# Regulators.net
KiCad netlist of a schematic drawn in Altium Designer
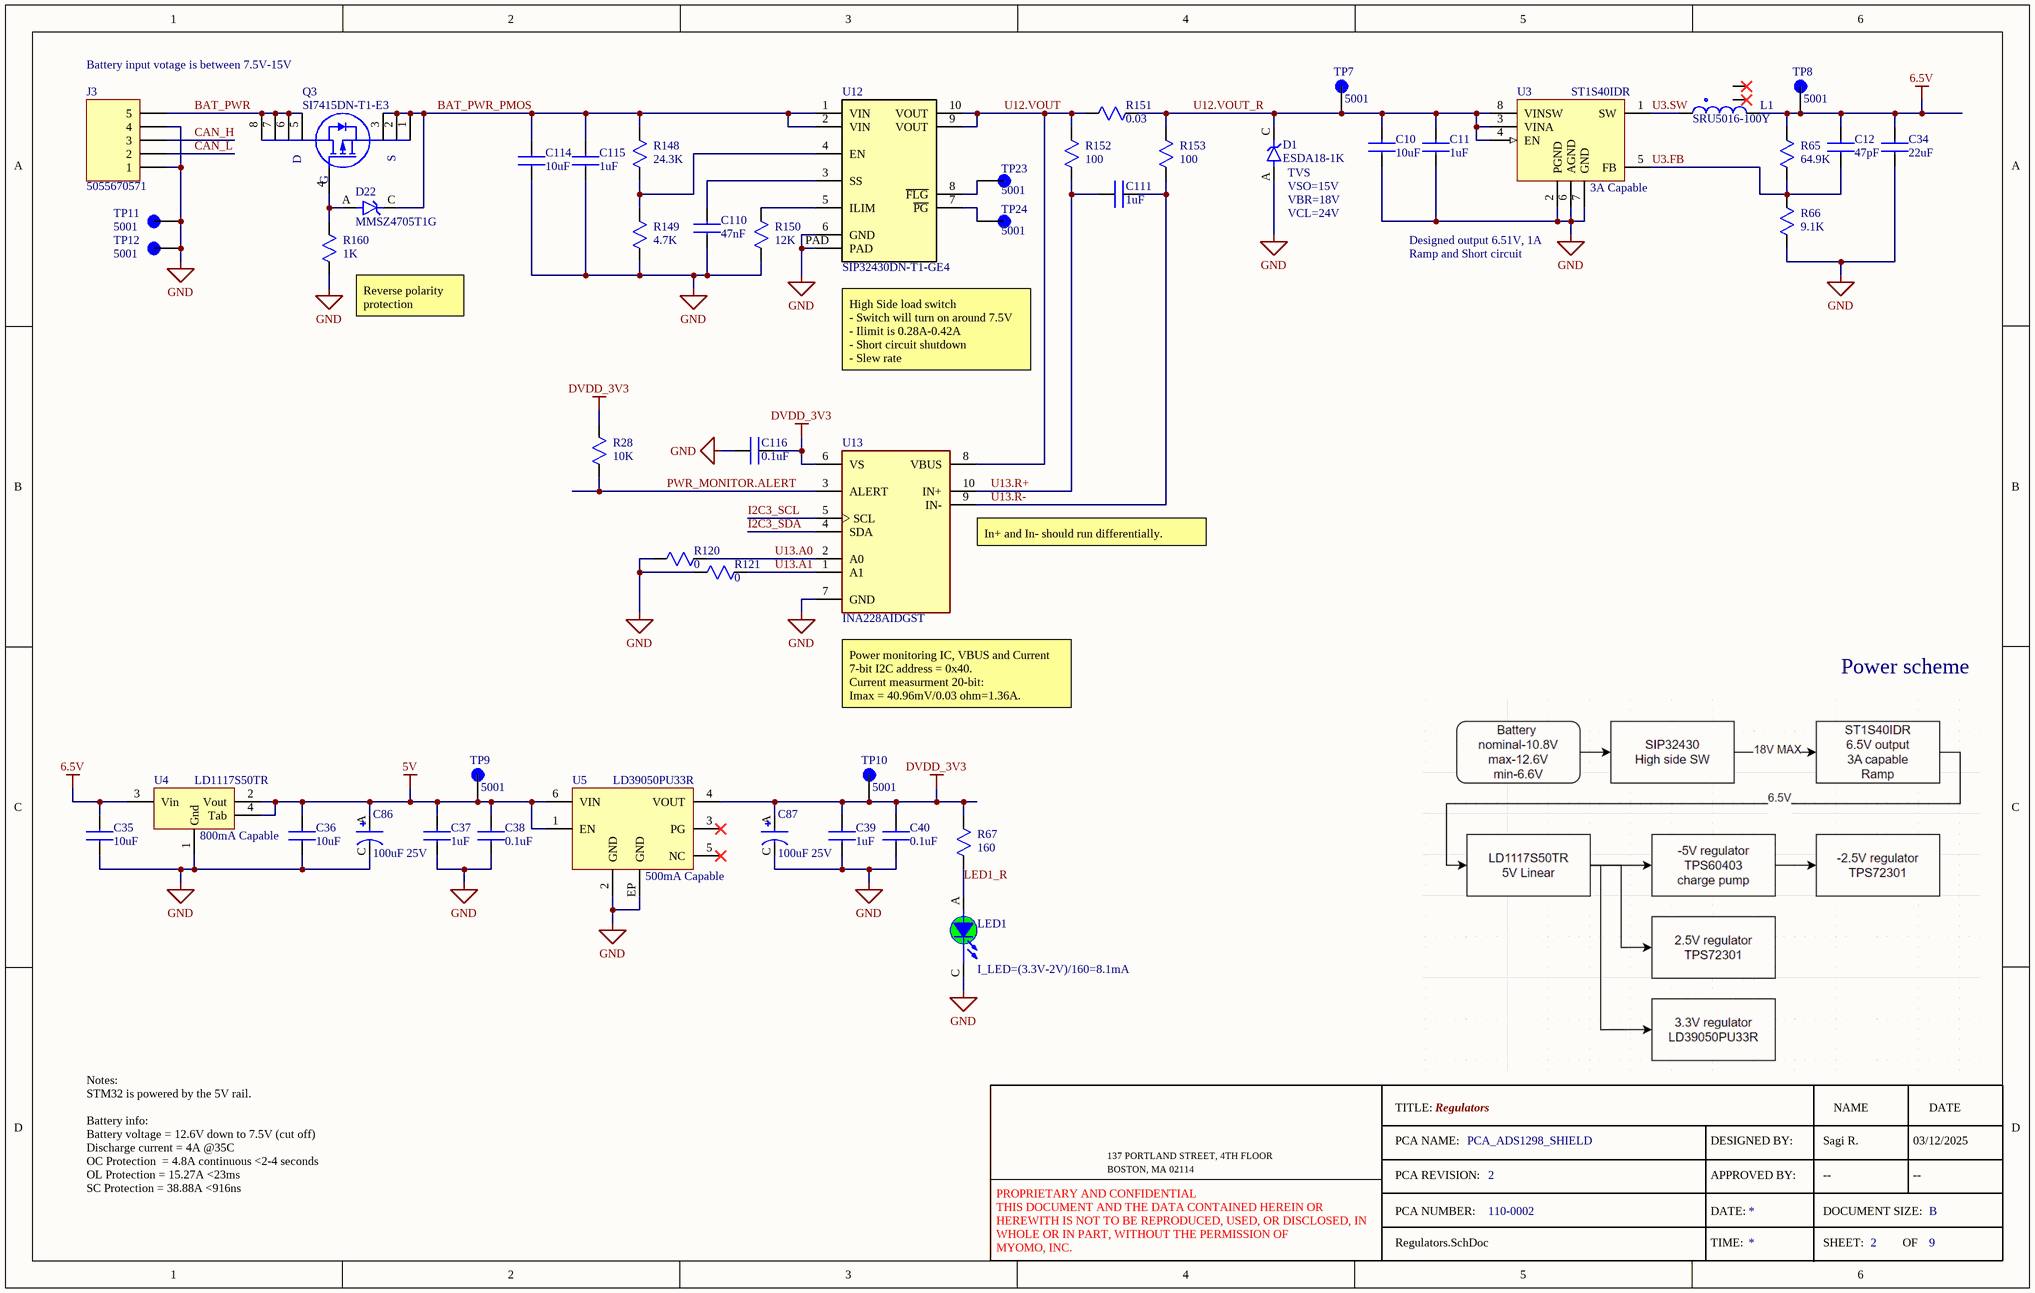
[diagram p0: Regulators.SchDoc]

(export (version "E")
  (design (tool "Eeschema 10.0.6"))
  (components
    (comp (ref "C10")
      (value "10uF")
      (footprint "1210")
      (description "CAP CER 10UF 25V X7R 1210")
      (fields (field (name "MFG") "SUMSUNG"))
      (libsource (lib "Myomo_SCH_Library") (part "C_1210_CER_10uF_25V_X7R"))
    )
    (comp (ref "C11")
      (value "1uF")
      (footprint "0603")
      (description "CAP CER 1UF 50V X7R 0603")
      (fields (field (name "MFG") "YAGEO"))
      (libsource (lib "Myomo_SCH_Library") (part "C_0603_CER_1uF_50V_X7R"))
    )
    (comp (ref "C12")
      (value "47pF")
      (footprint "0603")
      (description "CAP CER 47PF 100V C0G/NP0 0603")
      (fields (field (name "MFG") "KEMET"))
      (libsource (lib "Myomo_SCH_Library") (part "C_0603_CER_47pF_100V_COG"))
    )
    (comp (ref "C34")
      (value "22uF")
      (footprint "1210")
      (description "CAP CER 22UF 25V X7R 1210")
      (fields (field (name "MFG") "SUMSUNG"))
      (libsource (lib "Myomo_SCH_Library") (part "C_1210_CER_22uF_25V_X7R"))
    )
    (comp (ref "C35")
      (value "10uF")
      (footprint "1210")
      (description "CAP CER 10UF 25V X7R 1210")
      (fields (field (name "MFG") "SUMSUNG"))
      (libsource (lib "Myomo_SCH_Library") (part "C_1210_CER_10uF_25V_X7R"))
    )
    (comp (ref "C36")
      (value "10uF")
      (footprint "1210")
      (description "CAP CER 10UF 25V X7R 1210")
      (fields (field (name "MFG") "SUMSUNG"))
      (libsource (lib "Myomo_SCH_Library") (part "C_1210_CER_10uF_25V_X7R"))
    )
    (comp (ref "C37")
      (value "1uF")
      (footprint "0603")
      (description "CAP CER 1UF 50V X7R 0603")
      (fields (field (name "MFG") "YAGEO"))
      (libsource (lib "Myomo_SCH_Library") (part "C_0603_CER_1uF_50V_X7R"))
    )
    (comp (ref "C38")
      (value "0.1uF")
      (footprint "0402")
      (description "CAP CER 0.1UF 50V X7R 0402")
      (fields (field (name "MFG") "Samsung"))
      (libsource (lib "Myomo_SCH_Library") (part "C_0402_CER_0.1uF_50V_X7R"))
    )
    (comp (ref "C39")
      (value "1uF")
      (footprint "0603")
      (description "CAP CER 1UF 50V X7R 0603")
      (fields (field (name "MFG") "YAGEO"))
      (libsource (lib "Myomo_SCH_Library") (part "C_0603_CER_1uF_50V_X7R"))
    )
    (comp (ref "C40")
      (value "0.1uF")
      (footprint "0402")
      (description "CAP CER 0.1UF 50V X7R 0402")
      (fields (field (name "MFG") "Samsung"))
      (libsource (lib "Myomo_SCH_Library") (part "C_0402_CER_0.1uF_50V_X7R"))
    )
    (comp (ref "C86")
      (value "100uF 25V")
      (footprint "C_2917_TANT_100uF_25V")
      (description "CAP TANT POLY 100UF 25V 2917")
      (fields (field (name "MFG") "AVX Corporation"))
      (libsource (lib "Myomo_SCH_Library") (part "C_2917_TANT_100uF_25V"))
    )
    (comp (ref "C87")
      (value "100uF 25V")
      (footprint "C_2917_TANT_100uF_25V")
      (description "CAP TANT POLY 100UF 25V 2917")
      (fields (field (name "MFG") "AVX Corporation"))
      (libsource (lib "Myomo_SCH_Library") (part "C_2917_TANT_100uF_25V"))
    )
    (comp (ref "C110")
      (value "47nF")
      (footprint "0402")
      (description "CAP CER 47nF 50V X7R 0402")
      (fields (field (name "MFG") "TDK"))
      (libsource (lib "Myomo_SCH_Library") (part "C_0402_CER_47nF_50V_X7R"))
    )
    (comp (ref "C111")
      (value "1uF")
      (footprint "0603")
      (description "CAP CER 1UF 50V X7R 0603")
      (fields (field (name "MFG") "YAGEO"))
      (libsource (lib "") (part "C_0603_CER_1uF_50V_X7R_1"))
    )
    (comp (ref "C114")
      (value "10uF")
      (footprint "1210")
      (description "CAP CER 10UF 25V X7R 1210")
      (fields (field (name "MFG") "SUMSUNG"))
      (libsource (lib "Myomo_SCH_Library") (part "C_1210_CER_10uF_25V_X7R"))
    )
    (comp (ref "C115")
      (value "1uF")
      (footprint "0603")
      (description "CAP CER 1UF 50V X7R 0603")
      (fields (field (name "MFG") "YAGEO"))
      (libsource (lib "Myomo_SCH_Library") (part "C_0603_CER_1uF_50V_X7R"))
    )
    (comp (ref "C116")
      (value "0.1uF")
      (footprint "0402")
      (description "CAP CER 0.1UF 50V X7R 0402")
      (fields (field (name "MFG") "Samsung"))
      (libsource (lib "") (part "C_0402_CER_0.1uF_50V_X7R_1"))
    )
    (comp (ref "D1")
      (value "ESDA18-1K")
      (footprint "D_TVS_18V_400W")
      (description "TVS DIODE 15VWM 34VC SOD523")
      (fields (field (name "MFG") "STMicroelectronics"))
      (libsource (lib "Myomo_SCH_Library") (part "D_TVS_18V_400W"))
    )
    (comp (ref "D22")
      (value "MMSZ4705T1G")
      (footprint "D_ZENER_18V_500mW")
      (description "DIODE ZENER 18V 500MW SOD123")
      (fields (field (name "MFG") "Onsemi"))
      (libsource (lib "Myomo_SCH_Library") (part "D_ZENER_18V_500mW"))
    )
    (comp (ref "J3")
      (value "5055670571")
      (footprint "J_MOLEX_5055670571")
      (description "CONN HEADER SMD R/A 5POS 1.25MM")
      (fields (field (name "MFG") "Molex"))
      (libsource (lib "Myomo_SCH_Library") (part "J_MOLEX_5055670571"))
    )
    (comp (ref "L1")
      (value "SRU5016-100Y")
      (footprint "L_10UH_84m_1A")
      (description "FIXED IND 10UH 1A 84 MOHM SMD")
      (fields (field (name "MFG") "Bourns Inc."))
      (libsource (lib "Myomo_SCH_Library") (part "L_10UH_84m_1A"))
    )
    (comp (ref "LED1")
      (value "D_LED_GREEN_LTST")
      (footprint "D_LED_GREEN_LTST")
      (description "LED GREEN CLEAR 0603 SMD")
      (fields (field (name "MFG") "Lite-On Inc."))
      (libsource (lib "Myomo_SCH_Library") (part "D_LED_GREEN_LTST"))
    )
    (comp (ref "Q3")
      (value "SI7415DN-T1-E3")
      (footprint "Q_PMOSFET_SI7415DN-T1-E3")
      (description "MOSFET P-CH 60V 3.6A PPAK1212-8")
      (fields (field (name "MFG") "Vishay"))
      (libsource (lib "Myomo_SCH_Library") (part "Q_PMOSFET_SI7415DN-T1-E3"))
    )
    (comp (ref "R28")
      (value "10K")
      (footprint "0402")
      (description "RES SMD 10K OHM 1% 1/10W 0402")
      (fields (field (name "MFG") "Panasonic"))
      (libsource (lib "Myomo_SCH_Library") (part "R_0402_10K_1%_1/10W"))
    )
    (comp (ref "R65")
      (value "64.9K")
      (footprint "0603")
      (description "RES 64.9K OHM 1% 1/10W 0603")
      (fields (field (name "MFG") "YAGEO"))
      (libsource (lib "Myomo_SCH_Library") (part "R_0603_64.9K_1%_1/10W"))
    )
    (comp (ref "R66")
      (value "9.1K")
      (footprint "0603")
      (description "RES 9.1K OHM 1% 1/10W 0603")
      (fields (field (name "MFG") "YAGEO"))
      (libsource (lib "Myomo_SCH_Library") (part "R_0603_9.1K_1%_1/10W"))
    )
    (comp (ref "R67")
      (value "160")
      (footprint "0603")
      (description "RES 160 OHM 1% 1/10W 0603")
      (fields (field (name "MFG") "YAGEO"))
      (libsource (lib "Myomo_SCH_Library") (part "R_0603_160_1%_1/10W"))
    )
    (comp (ref "R120")
      (value "0")
      (footprint "0402")
      (description "RES 0 OHM JUMPER 1/10W 0402")
      (fields (field (name "MFG") "YAGEO"))
      (libsource (lib "Myomo_SCH_Library") (part "R_0402_0"))
    )
    (comp (ref "R121")
      (value "0")
      (footprint "0402")
      (description "RES 0 OHM JUMPER 1/10W 0402")
      (fields (field (name "MFG") "YAGEO"))
      (libsource (lib "Myomo_SCH_Library") (part "R_0402_0"))
    )
    (comp (ref "R148")
      (value "24.3K")
      (footprint "0402")
      (description "RES SMD 24.3K OHM 1% 1/10W 0402")
      (fields (field (name "MFG") "Panasonic"))
      (libsource (lib "Myomo_SCH_Library") (part "R_0402_24.3K_1%_1/10W"))
    )
    (comp (ref "R149")
      (value "4.7K")
      (footprint "0402")
      (description "RES SMD 4.7K OHM 1% 1/10W 0402")
      (fields (field (name "MFG") "Panasonic"))
      (libsource (lib "Myomo_SCH_Library") (part "R_0402_4.7K_1%_1/10W"))
    )
    (comp (ref "R150")
      (value "12K")
      (footprint "0402")
      (description "RES SMD 12K OHM 1% 1/10W 0402")
      (fields (field (name "MFG") "Panasonic"))
      (libsource (lib "Myomo_SCH_Library") (part "R_0402_12K_1%_1/10W"))
    )
    (comp (ref "R151")
      (value "0.03")
      (footprint "1206")
      (description "RES 0.03 OHM 0.5% 1W 1206")
      (fields (field (name "MFG") "Vishay"))
      (libsource (lib "Myomo_SCH_Library") (part "R_1206_0.03_0.5%_1W"))
    )
    (comp (ref "R152")
      (value "100")
      (footprint "0402")
      (description "RES SMD 100 OHM 1% 1/10W 0402")
      (fields (field (name "MFG") "Panasonic"))
      (libsource (lib "Myomo_SCH_Library") (part "R_0402_100_1%_1/10W"))
    )
    (comp (ref "R153")
      (value "100")
      (footprint "0402")
      (description "RES SMD 100 OHM 1% 1/10W 0402")
      (fields (field (name "MFG") "Panasonic"))
      (libsource (lib "Myomo_SCH_Library") (part "R_0402_100_1%_1/10W"))
    )
    (comp (ref "R160")
      (value "1K")
      (footprint "0603")
      (description "RES 1K OHM 1% 1/10W 0603")
      (fields (field (name "MFG") "YAGEO"))
      (libsource (lib "Myomo_SCH_Library") (part "R_0603_1K_1%_1/10W"))
    )
    (comp (ref "TP7")
      (value "5001")
      (footprint "TP_CLIP_BLK_5001")
      (description "PC TEST POINT MINIATURE BLACK")
      (fields (field (name "MFG") "Keystone Electronics"))
      (libsource (lib "Myomo_SCH_Library") (part "TP_CLIP_BLK_5001"))
    )
    (comp (ref "TP8")
      (value "5001")
      (footprint "TP_CLIP_BLK_5001")
      (description "PC TEST POINT MINIATURE BLACK")
      (fields (field (name "MFG") "Keystone Electronics"))
      (libsource (lib "Myomo_SCH_Library") (part "TP_CLIP_BLK_5001"))
    )
    (comp (ref "TP9")
      (value "5001")
      (footprint "TP_CLIP_BLK_5001")
      (description "PC TEST POINT MINIATURE BLACK")
      (fields (field (name "MFG") "Keystone Electronics"))
      (libsource (lib "Myomo_SCH_Library") (part "TP_CLIP_BLK_5001"))
    )
    (comp (ref "TP10")
      (value "5001")
      (footprint "TP_CLIP_BLK_5001")
      (description "PC TEST POINT MINIATURE BLACK")
      (fields (field (name "MFG") "Keystone Electronics"))
      (libsource (lib "Myomo_SCH_Library") (part "TP_CLIP_BLK_5001"))
    )
    (comp (ref "TP11")
      (value "5001")
      (footprint "TP_CLIP_BLK_5001")
      (description "PC TEST POINT MINIATURE BLACK")
      (fields (field (name "MFG") "Keystone Electronics"))
      (libsource (lib "Myomo_SCH_Library") (part "TP_CLIP_BLK_5001"))
    )
    (comp (ref "TP12")
      (value "5001")
      (footprint "TP_CLIP_BLK_5001")
      (description "PC TEST POINT MINIATURE BLACK")
      (fields (field (name "MFG") "Keystone Electronics"))
      (libsource (lib "Myomo_SCH_Library") (part "TP_CLIP_BLK_5001"))
    )
    (comp (ref "TP23")
      (value "5001")
      (footprint "TP_CLIP_BLK_5001")
      (description "PC TEST POINT MINIATURE BLACK")
      (fields (field (name "MFG") "Keystone Electronics"))
      (libsource (lib "Myomo_SCH_Library") (part "TP_CLIP_BLK_5001"))
    )
    (comp (ref "TP24")
      (value "5001")
      (footprint "TP_CLIP_BLK_5001")
      (description "PC TEST POINT MINIATURE BLACK")
      (fields (field (name "MFG") "Keystone Electronics"))
      (libsource (lib "Myomo_SCH_Library") (part "TP_CLIP_BLK_5001"))
    )
    (comp (ref "U3")
      (value "ST1S40IDR")
      (footprint "U_ST1S40IDR")
      (description "IC REG BUCK ADJ 3A 8SOIC")
      (fields (field (name "MFG") "STMicroelectronics"))
      (libsource (lib "Myomo_SCH_Library") (part "U_ST1S40IDR"))
    )
    (comp (ref "U4")
      (value "LD1117S50TR")
      (footprint "U_LD1117S50TR")
      (description "IC REG LINEAR 5V 800MA SOT223")
      (fields (field (name "MFG") "STMICROELECTRONICS"))
      (libsource (lib "Myomo_SCH_Library") (part "U_LD1117S50TR"))
    )
    (comp (ref "U5")
      (value "LD39050PU33R")
      (footprint "U_LD39050PU33R")
      (description "IC REG LINEAR 3.3V 500MA 6DFN")
      (fields (field (name "MFG") "STMICROELECTRONICS"))
      (libsource (lib "Myomo_SCH_Library") (part "U_LD39050PU33R"))
    )
    (comp (ref "U12")
      (value "SIP32430DN-T1-GE4")
      (footprint "U_SIP32430DN-T1-GE4")
      (description "HIGH SIDE SWITCH - IC PWR SWITCH P-CHAN 1:1 10DFN")
      (fields (field (name "MFG") "Vishay"))
      (libsource (lib "Myomo_SCH_Library") (part "U_SIP32430DN-T1-GE4"))
    )
    (comp (ref "U13")
      (value "INA228AIDGST")
      (footprint "U_INA228AIDGS")
      (description "IC REG BUCK ADJ 3A 8SOIC")
      (fields (field (name "MFG") "TI"))
      (libsource (lib "Myomo_SCH_Library") (part "U_INA228AIDGS"))
    )
  )
  (nets
    (net (code "1") (name "/BAT_PWR") (class "Default")
      (node (ref "J3") (pin "5") (pinfunction "5_5") (pintype "passive"))
      (node (ref "Q3") (pin "5") (pinfunction "D_5") (pintype "passive"))
      (node (ref "Q3") (pin "6") (pinfunction "D_6") (pintype "passive"))
      (node (ref "Q3") (pin "7") (pinfunction "D_7") (pintype "passive"))
      (node (ref "Q3") (pin "8") (pinfunction "D_8") (pintype "passive"))
    )
    (net (code "2") (name "/BAT_PWR_PMOS") (class "Default")
      (node (ref "C114") (pin "1") (pinfunction "1_1") (pintype "passive"))
      (node (ref "C115") (pin "1") (pinfunction "1_1") (pintype "passive"))
      (node (ref "D22") (pin "C") (pinfunction "C_C") (pintype "passive"))
      (node (ref "Q3") (pin "1") (pinfunction "S_1") (pintype "passive"))
      (node (ref "Q3") (pin "2") (pinfunction "S_2") (pintype "passive"))
      (node (ref "Q3") (pin "3") (pinfunction "S_3") (pintype "passive"))
      (node (ref "R148") (pin "1") (pinfunction "1_1") (pintype "passive"))
      (node (ref "U12") (pin "1") (pinfunction "VIN_1") (pintype "passive"))
      (node (ref "U12") (pin "2") (pinfunction "VIN_2") (pintype "passive"))
    )
    (net (code "3") (name "/CAN_H") (class "Default")
      (node (ref "J3") (pin "3") (pinfunction "3_3") (pintype "passive"))
    )
    (net (code "4") (name "/CAN_L") (class "Default")
      (node (ref "J3") (pin "2") (pinfunction "2_2") (pintype "passive"))
    )
    (net (code "5") (name "/I2C3_SCL") (class "Default")
      (node (ref "U13") (pin "5") (pinfunction "SCL_5") (pintype "passive"))
    )
    (net (code "6") (name "/I2C3_SDA") (class "Default")
      (node (ref "U13") (pin "4") (pinfunction "SDA_4") (pintype "passive"))
    )
    (net (code "7") (name "/LED1_R") (class "Default")
      (node (ref "LED1") (pin "A") (pinfunction "ANODE_A") (pintype "passive"))
      (node (ref "R67") (pin "2") (pinfunction "2_2") (pintype "passive"))
    )
    (net (code "8") (name "/PWR_MONITOR.ALERT") (class "Default")
      (node (ref "R28") (pin "2") (pinfunction "2_2") (pintype "passive"))
      (node (ref "U13") (pin "3") (pinfunction "ALERT_3") (pintype "passive"))
    )
    (net (code "9") (name "/U3.FB") (class "Default")
      (node (ref "C12") (pin "2") (pinfunction "2_2") (pintype "passive"))
      (node (ref "R65") (pin "2") (pinfunction "2_2") (pintype "passive"))
      (node (ref "R66") (pin "1") (pinfunction "1_1") (pintype "passive"))
      (node (ref "U3") (pin "5") (pinfunction "FB_5") (pintype "power_in"))
    )
    (net (code "10") (name "/U3.SW") (class "Default")
      (node (ref "L1") (pin "1") (pinfunction "1_1") (pintype "passive"))
      (node (ref "U3") (pin "1") (pinfunction "SW_1") (pintype "power_in"))
    )
    (net (code "11") (name "/U12.VOUT") (class "Default")
      (node (ref "R151") (pin "1") (pinfunction "1_1") (pintype "passive"))
      (node (ref "R152") (pin "1") (pinfunction "1_1") (pintype "passive"))
      (node (ref "U12") (pin "10") (pinfunction "VOUT_10") (pintype "passive"))
      (node (ref "U12") (pin "9") (pinfunction "VOUT_9") (pintype "passive"))
      (node (ref "U13") (pin "8") (pinfunction "VBUS_8") (pintype "passive"))
    )
    (net (code "12") (name "/U12.VOUT_R") (class "Default")
      (node (ref "C10") (pin "1") (pinfunction "1_1") (pintype "passive"))
      (node (ref "C11") (pin "1") (pinfunction "1_1") (pintype "passive"))
      (node (ref "D1") (pin "C") (pinfunction "C_C") (pintype "passive"))
      (node (ref "R151") (pin "2") (pinfunction "2_2") (pintype "passive"))
      (node (ref "R153") (pin "1") (pinfunction "1_1") (pintype "passive"))
      (node (ref "TP7") (pin "TP") (pinfunction "TP_TP") (pintype "passive"))
      (node (ref "U3") (pin "3") (pinfunction "VINA_3") (pintype "power_in"))
      (node (ref "U3") (pin "4") (pinfunction "EN_4") (pintype "input"))
      (node (ref "U3") (pin "8") (pinfunction "VINSW_8") (pintype "power_in"))
    )
    (net (code "13") (name "/U13.A0") (class "Default")
      (node (ref "R120") (pin "2") (pinfunction "2_2") (pintype "passive"))
      (node (ref "U13") (pin "2") (pinfunction "A0_2") (pintype "passive"))
    )
    (net (code "14") (name "/U13.A1") (class "Default")
      (node (ref "R121") (pin "2") (pinfunction "2_2") (pintype "passive"))
      (node (ref "U13") (pin "1") (pinfunction "A1_1") (pintype "passive"))
    )
    (net (code "15") (name "/U13.R+") (class "Default")
      (node (ref "C111") (pin "1") (pinfunction "1_1") (pintype "passive"))
      (node (ref "R152") (pin "2") (pinfunction "2_2") (pintype "passive"))
      (node (ref "U13") (pin "10") (pinfunction "IN+_10") (pintype "passive"))
    )
    (net (code "16") (name "/U13.R-") (class "Default")
      (node (ref "C111") (pin "2") (pinfunction "2_2") (pintype "passive"))
      (node (ref "R153") (pin "2") (pinfunction "2_2") (pintype "passive"))
      (node (ref "U13") (pin "9") (pinfunction "IN-_9") (pintype "passive"))
    )
    (net (code "17") (name "5V") (class "Default")
      (node (ref "C36") (pin "1") (pinfunction "1_1") (pintype "passive"))
      (node (ref "C37") (pin "1") (pinfunction "1_1") (pintype "passive"))
      (node (ref "C38") (pin "1") (pinfunction "1_1") (pintype "passive"))
      (node (ref "C86") (pin "A") (pinfunction "A_A") (pintype "passive"))
      (node (ref "TP9") (pin "TP") (pinfunction "TP_TP") (pintype "passive"))
      (node (ref "U4") (pin "2") (pinfunction "Vout_2") (pintype "passive"))
      (node (ref "U4") (pin "4") (pinfunction "Tab_4") (pintype "passive"))
      (node (ref "U5") (pin "1") (pinfunction "EN_1") (pintype "passive"))
      (node (ref "U5") (pin "6") (pinfunction "VIN_6") (pintype "passive"))
    )
    (net (code "18") (name "6.5V") (class "Default")
      (node (ref "C12") (pin "1") (pinfunction "1_1") (pintype "passive"))
      (node (ref "C34") (pin "1") (pinfunction "1_1") (pintype "passive"))
      (node (ref "C35") (pin "1") (pinfunction "1_1") (pintype "passive"))
      (node (ref "L1") (pin "2") (pinfunction "2_2") (pintype "passive"))
      (node (ref "R65") (pin "1") (pinfunction "1_1") (pintype "passive"))
      (node (ref "TP8") (pin "TP") (pinfunction "TP_TP") (pintype "passive"))
      (node (ref "U4") (pin "3") (pinfunction "Vin_3") (pintype "passive"))
    )
    (net (code "19") (name "DVDD_3V3") (class "Default")
      (node (ref "C116") (pin "2") (pinfunction "2_2") (pintype "passive"))
      (node (ref "C39") (pin "1") (pinfunction "1_1") (pintype "passive"))
      (node (ref "C40") (pin "1") (pinfunction "1_1") (pintype "passive"))
      (node (ref "C87") (pin "A") (pinfunction "A_A") (pintype "passive"))
      (node (ref "R28") (pin "1") (pinfunction "1_1") (pintype "passive"))
      (node (ref "R67") (pin "1") (pinfunction "1_1") (pintype "passive"))
      (node (ref "TP10") (pin "TP") (pinfunction "TP_TP") (pintype "passive"))
      (node (ref "U13") (pin "6") (pinfunction "VS_6") (pintype "power_in"))
      (node (ref "U5") (pin "4") (pinfunction "VOUT_4") (pintype "passive"))
    )
    (net (code "20") (name "GND") (class "Default")
      (node (ref "C10") (pin "2") (pinfunction "2_2") (pintype "passive"))
      (node (ref "C11") (pin "2") (pinfunction "2_2") (pintype "passive"))
      (node (ref "C110") (pin "2") (pinfunction "2_2") (pintype "passive"))
      (node (ref "C114") (pin "2") (pinfunction "2_2") (pintype "passive"))
      (node (ref "C115") (pin "2") (pinfunction "2_2") (pintype "passive"))
      (node (ref "C116") (pin "1") (pinfunction "1_1") (pintype "passive"))
      (node (ref "C34") (pin "2") (pinfunction "2_2") (pintype "passive"))
      (node (ref "C35") (pin "2") (pinfunction "2_2") (pintype "passive"))
      (node (ref "C36") (pin "2") (pinfunction "2_2") (pintype "passive"))
      (node (ref "C37") (pin "2") (pinfunction "2_2") (pintype "passive"))
      (node (ref "C38") (pin "2") (pinfunction "2_2") (pintype "passive"))
      (node (ref "C39") (pin "2") (pinfunction "2_2") (pintype "passive"))
      (node (ref "C40") (pin "2") (pinfunction "2_2") (pintype "passive"))
      (node (ref "C86") (pin "C") (pinfunction "C_C") (pintype "passive"))
      (node (ref "C87") (pin "C") (pinfunction "C_C") (pintype "passive"))
      (node (ref "D1") (pin "A") (pinfunction "A_A") (pintype "passive"))
      (node (ref "J3") (pin "1") (pinfunction "1_1") (pintype "passive"))
      (node (ref "J3") (pin "4") (pinfunction "4_4") (pintype "passive"))
      (node (ref "LED1") (pin "C") (pinfunction "CATHODE_C") (pintype "passive"))
      (node (ref "R120") (pin "1") (pinfunction "1_1") (pintype "passive"))
      (node (ref "R121") (pin "1") (pinfunction "1_1") (pintype "passive"))
      (node (ref "R149") (pin "2") (pinfunction "2_2") (pintype "passive"))
      (node (ref "R150") (pin "2") (pinfunction "2_2") (pintype "passive"))
      (node (ref "R160") (pin "2") (pinfunction "2_2") (pintype "passive"))
      (node (ref "R66") (pin "2") (pinfunction "2_2") (pintype "passive"))
      (node (ref "TP11") (pin "TP") (pinfunction "TP_TP") (pintype "passive"))
      (node (ref "TP12") (pin "TP") (pinfunction "TP_TP") (pintype "passive"))
      (node (ref "U12") (pin "6") (pinfunction "GND_6") (pintype "passive"))
      (node (ref "U12") (pin "PAD") (pinfunction "PAD_PAD") (pintype "passive"))
      (node (ref "U13") (pin "7") (pinfunction "GND_7") (pintype "power_in"))
      (node (ref "U3") (pin "2") (pinfunction "PGND_2") (pintype "power_in"))
      (node (ref "U3") (pin "6") (pinfunction "AGND_6") (pintype "power_in"))
      (node (ref "U3") (pin "7") (pinfunction "GND_7") (pintype "power_in"))
      (node (ref "U4") (pin "1") (pinfunction "Gnd_1") (pintype "passive"))
      (node (ref "U5") (pin "2") (pinfunction "GND_2") (pintype "passive"))
      (node (ref "U5") (pin "EP") (pinfunction "GND_EP") (pintype "passive"))
    )
    (net (code "21") (name "Net-(Q3-G)") (class "Default")
      (node (ref "D22") (pin "A") (pinfunction "A_A") (pintype "passive"))
      (node (ref "Q3") (pin "4") (pinfunction "G_4") (pintype "passive"))
      (node (ref "R160") (pin "1") (pinfunction "1_1") (pintype "passive"))
    )
    (net (code "22") (name "Net-(U12-EN)") (class "Default")
      (node (ref "R148") (pin "2") (pinfunction "2_2") (pintype "passive"))
      (node (ref "R149") (pin "1") (pinfunction "1_1") (pintype "passive"))
      (node (ref "U12") (pin "4") (pinfunction "EN_4") (pintype "passive"))
    )
    (net (code "23") (name "Net-(U12-ILIM)") (class "Default")
      (node (ref "R150") (pin "1") (pinfunction "1_1") (pintype "passive"))
      (node (ref "U12") (pin "5") (pinfunction "ILIM_5") (pintype "passive"))
    )
    (net (code "24") (name "Net-(U12-SS)") (class "Default")
      (node (ref "C110") (pin "1") (pinfunction "1_1") (pintype "passive"))
      (node (ref "U12") (pin "3") (pinfunction "SS_3") (pintype "passive"))
    )
    (net (code "25") (name "Net-(U12-~{FLG})") (class "Default")
      (node (ref "TP23") (pin "TP") (pinfunction "TP_TP") (pintype "passive"))
      (node (ref "U12") (pin "8") (pinfunction "~{FLG}_8") (pintype "passive"))
    )
    (net (code "26") (name "Net-(U12-~{PG})") (class "Default")
      (node (ref "TP24") (pin "TP") (pinfunction "TP_TP") (pintype "passive"))
      (node (ref "U12") (pin "7") (pinfunction "~{PG}_7") (pintype "passive"))
    )
    (net (code "27") (name "unconnected-(L1-PadMH1)") (class "Default")
      (node (ref "L1") (pin "MH1") (pinfunction "MH1_MH1") (pintype "passive+no_connect"))
    )
    (net (code "28") (name "unconnected-(L1-PadMH2)") (class "Default")
      (node (ref "L1") (pin "MH2") (pinfunction "MH2_MH2") (pintype "passive+no_connect"))
    )
    (net (code "29") (name "unconnected-(U5-NC-Pad5)") (class "Default")
      (node (ref "U5") (pin "5") (pinfunction "NC_5") (pintype "passive+no_connect"))
    )
    (net (code "30") (name "unconnected-(U5-PG-Pad3)") (class "Default")
      (node (ref "U5") (pin "3") (pinfunction "PG_3") (pintype "passive+no_connect"))
    )
  )
)
